# Motor-Z.net
KiCad netlist of a schematic drawn in Altium Designer
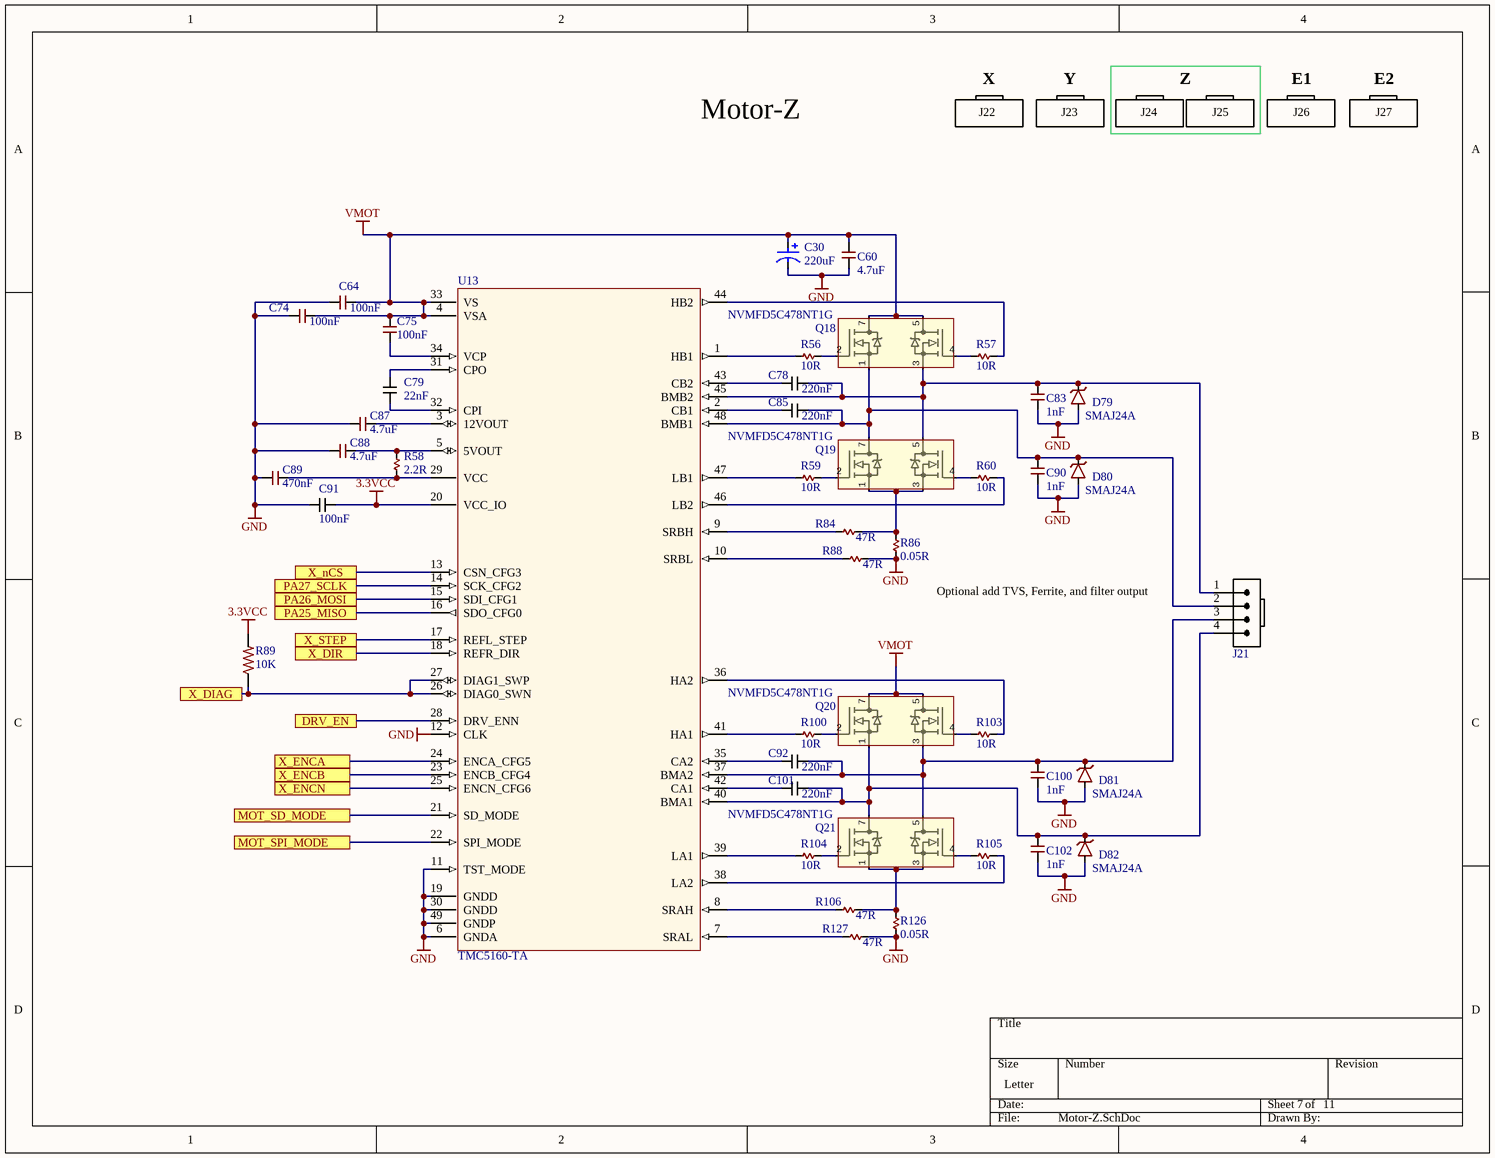
[diagram p0: Motor-Z.SchDoc]

(export (version "E")
  (design (tool "Eeschema 10.0.6"))
  (components
    (comp (ref "C30")
      (value "220uF")
      (footprint "CAP10X10")
      (description "CAP ALUM 220UF 20% 50V SMD")
      (fields (field (name "MANUFACTURER") "Nichicon") (field (name "TOLERANCE") "20%"))
      (libsource (lib "Capacitors") (part "220uF Al-El 50V"))
    )
    (comp (ref "C60")
      (value "4.7uF")
      (footprint "C1206")
      (description "CAP CER 1206 4.7uF 50V 10% X5R")
      (fields (field (name "MANUFACTURER") "Kemet") (field (name "PART") "4.7uF 50V X5R 1206"))
      (libsource (lib "Capacitors") (part "4.7uF 1206 50V X5R"))
    )
    (comp (ref "C64")
      (value "100nF")
      (footprint "C0603")
      (description "CAP CER 0603 100nF 50V 10% X7R")
      (fields (field (name "MANUFACTURER") "Kemet") (field (name "PART") "100nF 50V X7R 0603"))
      (libsource (lib "Capacitors") (part "100nF 0603 50V X7R"))
    )
    (comp (ref "C74")
      (value "100nF")
      (footprint "C0603")
      (description "CAP CER 0603 100nF 50V 10% X7R")
      (fields (field (name "MANUFACTURER") "Kemet") (field (name "PART") "100nF 50V X7R 0603"))
      (libsource (lib "Capacitors") (part "100nF 0603 50V X7R"))
    )
    (comp (ref "C75")
      (value "100nF")
      (footprint "C0603")
      (description "CAP CER 0603 100nF 50V 10% X7R")
      (fields (field (name "MANUFACTURER") "Kemet") (field (name "PART") "100nF 50V X7R 0603"))
      (libsource (lib "Capacitors") (part "100nF 0603 50V X7R"))
    )
    (comp (ref "C78")
      (value "220nF")
      (footprint "C0603")
      (description "CAP CER 0.22UF 50V X7R 0603")
      (fields (field (name "MANUFACTURER") "TDK"))
      (libsource (lib "Capacitors") (part "220nF 50V X7R 0603"))
    )
    (comp (ref "C79")
      (value "22nF")
      (footprint "C0603")
      (description "CAP CER 0.022UF 100V X7R 0603")
      (fields (field (name "MANUFACTURER") "Kemet"))
      (libsource (lib "Capacitors") (part "22nF 100V X7R 0603"))
    )
    (comp (ref "C83")
      (value "1nF")
      (footprint "C0603")
      (description "CAP CER 0603  1nF 50v 10% X7R")
      (fields (field (name "MANUFACTURER") "Kemet") (field (name "TOLERANCE") "+/- 10%"))
      (libsource (lib "Capacitors") (part "1nF 50V X7R 0603"))
    )
    (comp (ref "C85")
      (value "220nF")
      (footprint "C0603")
      (description "CAP CER 0.22UF 50V X7R 0603")
      (fields (field (name "MANUFACTURER") "TDK"))
      (libsource (lib "Capacitors") (part "220nF 50V X7R 0603"))
    )
    (comp (ref "C87")
      (value "4.7uF")
      (footprint "C1206")
      (description "CAP CER 1206 4.7uF 50V 10% X5R")
      (fields (field (name "MANUFACTURER") "Kemet") (field (name "PART") "4.7uF 50V X5R 1206"))
      (libsource (lib "Capacitors") (part "4.7uF 1206 50V X5R"))
    )
    (comp (ref "C88")
      (value "4.7uF")
      (footprint "C0603")
      (description "CAP CER 4.7UF 6.3V X7R 0603")
      (fields (field (name "MANUFACTURER") "Samsung") (field (name "TOLERANCE") "10%"))
      (libsource (lib "Capacitors") (part "4.7uF 0603 6.3V X7R"))
    )
    (comp (ref "C89")
      (value "470nF")
      (footprint "3Delight:C0402")
      (description "470nF 6.3v C0402 - GRM155R60J474KE19D")
      (fields (field (name "TOLERANCE") "10%") (field (name "MANUFACTURER") "Murata"))
      (libsource (lib "Capacitors") (part "470nF 0402 6.3V X5R"))
    )
    (comp (ref "C90")
      (value "1nF")
      (footprint "C0603")
      (description "CAP CER 0603  1nF 50v 10% X7R")
      (fields (field (name "MANUFACTURER") "Kemet") (field (name "TOLERANCE") "+/- 10%"))
      (libsource (lib "Capacitors") (part "1nF 50V X7R 0603"))
    )
    (comp (ref "C91")
      (value "100nF")
      (footprint "C0201 Large Pads")
      (description "CAP CER 0.1UF 6.3V 10% X5R 0201")
      (fields (field (name "MANUFACTURER") "Samsung") (field (name "TOLERANCE") "10%"))
      (libsource (lib "Capacitors") (part "100nF 6.3V X5R 0201"))
    )
    (comp (ref "C92")
      (value "220nF")
      (footprint "C0603")
      (description "CAP CER 0.22UF 50V X7R 0603")
      (fields (field (name "MANUFACTURER") "TDK"))
      (libsource (lib "Capacitors") (part "220nF 50V X7R 0603"))
    )
    (comp (ref "C100")
      (value "1nF")
      (footprint "C0603")
      (description "CAP CER 0603  1nF 50v 10% X7R")
      (fields (field (name "MANUFACTURER") "Kemet") (field (name "TOLERANCE") "+/- 10%"))
      (libsource (lib "Capacitors") (part "1nF 50V X7R 0603"))
    )
    (comp (ref "C101")
      (value "220nF")
      (footprint "C0603")
      (description "CAP CER 0.22UF 50V X7R 0603")
      (fields (field (name "MANUFACTURER") "TDK"))
      (libsource (lib "Capacitors") (part "220nF 50V X7R 0603"))
    )
    (comp (ref "C102")
      (value "1nF")
      (footprint "C0603")
      (description "CAP CER 0603  1nF 50v 10% X7R")
      (fields (field (name "MANUFACTURER") "Kemet") (field (name "TOLERANCE") "+/- 10%"))
      (libsource (lib "Capacitors") (part "1nF 50V X7R 0603"))
    )
    (comp (ref "D79")
      (value "SMAJ24A")
      (footprint "SMA-SM")
      (description "TVS DIODE 24V 38.9V SMA")
      (fields (field (name "MANUFACTURER") "Bourns Inc"))
      (libsource (lib "Diodes") (part "SMAJ24A"))
    )
    (comp (ref "D80")
      (value "SMAJ24A")
      (footprint "SMA-SM")
      (description "TVS DIODE 24V 38.9V SMA")
      (fields (field (name "MANUFACTURER") "Bourns Inc"))
      (libsource (lib "Diodes") (part "SMAJ24A"))
    )
    (comp (ref "D81")
      (value "SMAJ24A")
      (footprint "SMA-SM")
      (description "TVS DIODE 24V 38.9V SMA")
      (fields (field (name "MANUFACTURER") "Bourns Inc"))
      (libsource (lib "Diodes") (part "SMAJ24A"))
    )
    (comp (ref "D82")
      (value "SMAJ24A")
      (footprint "SMA-SM")
      (description "TVS DIODE 24V 38.9V SMA")
      (fields (field (name "MANUFACTURER") "Bourns Inc"))
      (libsource (lib "Diodes") (part "SMAJ24A"))
    )
    (comp (ref "J21")
      (value "Molex 0705430003")
      (footprint "4POL254 PIN-IN-PASTE")
      (description "Molex 4 Pin Clip Connector - Pin In Paste footprint")
      (libsource (lib "Connectors") (part "Molex 0705430003 PIP"))
    )
    (comp (ref "Q18")
      (value "NVMFD5C478NT1G")
      (footprint "SO8FL-Dual (DFN8 5x6, 1.26P Dual Flag)")
      (description "40V 17 MOHM T6 S08FL DUAL")
      (fields (field (name "MANUFACTURER") "ON Semiconductor") (field (name "TOLERANCE") "-NA-"))
      (libsource (lib "Transistors") (part "NVMFD5C478NT1G"))
    )
    (comp (ref "Q19")
      (value "NVMFD5C478NT1G")
      (footprint "SO8FL-Dual (DFN8 5x6, 1.26P Dual Flag)")
      (description "40V 17 MOHM T6 S08FL DUAL")
      (fields (field (name "MANUFACTURER") "ON Semiconductor") (field (name "TOLERANCE") "-NA-"))
      (libsource (lib "Transistors") (part "NVMFD5C478NT1G"))
    )
    (comp (ref "Q20")
      (value "NVMFD5C478NT1G")
      (footprint "SO8FL-Dual (DFN8 5x6, 1.26P Dual Flag)")
      (description "40V 17 MOHM T6 S08FL DUAL")
      (fields (field (name "MANUFACTURER") "ON Semiconductor") (field (name "TOLERANCE") "-NA-"))
      (libsource (lib "Transistors") (part "NVMFD5C478NT1G"))
    )
    (comp (ref "Q21")
      (value "NVMFD5C478NT1G")
      (footprint "SO8FL-Dual (DFN8 5x6, 1.26P Dual Flag)")
      (description "40V 17 MOHM T6 S08FL DUAL")
      (fields (field (name "MANUFACTURER") "ON Semiconductor") (field (name "TOLERANCE") "-NA-"))
      (libsource (lib "Transistors") (part "NVMFD5C478NT1G"))
    )
    (comp (ref "R56")
      (value "10R")
      (footprint "R0402")
      (description "RES SMD 10 OHM 1% 1/16W 0402")
      (fields (field (name "MANUFACTURER") "Yageo") (field (name "PART") "10R 1% 0402"))
      (libsource (lib "Resistors") (part "10R 1% 0402"))
    )
    (comp (ref "R57")
      (value "10R")
      (footprint "R0402")
      (description "RES SMD 10 OHM 1% 1/16W 0402")
      (fields (field (name "MANUFACTURER") "Yageo") (field (name "PART") "10R 1% 0402"))
      (libsource (lib "Resistors") (part "10R 1% 0402"))
    )
    (comp (ref "R58")
      (value "2.2R")
      (footprint "R0402")
      (description "RES SMD 2.2 OHM 5% 1/16W 0402")
      (fields (field (name "MANUFACTURER") "Yageo") (field (name "TOLERANCE") "+/- 5%"))
      (libsource (lib "Resistors") (part "2.2R 5% 0402"))
    )
    (comp (ref "R59")
      (value "10R")
      (footprint "R0402")
      (description "RES SMD 10 OHM 1% 1/16W 0402")
      (fields (field (name "MANUFACTURER") "Yageo") (field (name "PART") "10R 1% 0402"))
      (libsource (lib "Resistors") (part "10R 1% 0402"))
    )
    (comp (ref "R60")
      (value "10R")
      (footprint "R0402")
      (description "RES SMD 10 OHM 1% 1/16W 0402")
      (fields (field (name "MANUFACTURER") "Yageo") (field (name "PART") "10R 1% 0402"))
      (libsource (lib "Resistors") (part "10R 1% 0402"))
    )
    (comp (ref "R84")
      (value "47R")
      (footprint "R0402")
      (description "RES 47 OHM 1% 1/16W 0402")
      (fields (field (name "MANUFACTURER") "Vishay Dale") (field (name "TOLERANCE") "+/- 1%"))
      (libsource (lib "Resistors") (part "47R 1% 0402"))
    )
    (comp (ref "R86")
      (value "0.05R")
      (footprint "R2512")
      (description "RES 0.05 OHM 1% 2W 2512")
      (fields (field (name "MANUFACTURER") "Stackpole") (field (name "TOLERANCE") "+/- 1%"))
      (libsource (lib "Resistors") (part "0.05R 1% 2512"))
    )
    (comp (ref "R88")
      (value "47R")
      (footprint "R0402")
      (description "RES 47 OHM 1% 1/16W 0402")
      (fields (field (name "MANUFACTURER") "Vishay Dale") (field (name "TOLERANCE") "+/- 1%"))
      (libsource (lib "Resistors") (part "47R 1% 0402"))
    )
    (comp (ref "R89")
      (value "10K")
      (footprint "R0402")
      (description "RES SMD 10K OHM 1% 1/16W 0402")
      (fields (field (name "MANUFACTURER") "Yageo") (field (name "PART") "10k 1% 0402"))
      (libsource (lib "3Delight") (part "RC0402FR-0710KP"))
    )
    (comp (ref "R100")
      (value "10R")
      (footprint "R0402")
      (description "RES SMD 10 OHM 1% 1/16W 0402")
      (fields (field (name "MANUFACTURER") "Yageo") (field (name "PART") "10R 1% 0402"))
      (libsource (lib "Resistors") (part "10R 1% 0402"))
    )
    (comp (ref "R103")
      (value "10R")
      (footprint "R0402")
      (description "RES SMD 10 OHM 1% 1/16W 0402")
      (fields (field (name "MANUFACTURER") "Yageo") (field (name "PART") "10R 1% 0402"))
      (libsource (lib "Resistors") (part "10R 1% 0402"))
    )
    (comp (ref "R104")
      (value "10R")
      (footprint "R0402")
      (description "RES SMD 10 OHM 1% 1/16W 0402")
      (fields (field (name "MANUFACTURER") "Yageo") (field (name "PART") "10R 1% 0402"))
      (libsource (lib "Resistors") (part "10R 1% 0402"))
    )
    (comp (ref "R105")
      (value "10R")
      (footprint "R0402")
      (description "RES SMD 10 OHM 1% 1/16W 0402")
      (fields (field (name "MANUFACTURER") "Yageo") (field (name "PART") "10R 1% 0402"))
      (libsource (lib "Resistors") (part "10R 1% 0402"))
    )
    (comp (ref "R106")
      (value "47R")
      (footprint "R0402")
      (description "RES 47 OHM 1% 1/16W 0402")
      (fields (field (name "MANUFACTURER") "Vishay Dale") (field (name "TOLERANCE") "+/- 1%"))
      (libsource (lib "Resistors") (part "47R 1% 0402"))
    )
    (comp (ref "R126")
      (value "0.05R")
      (footprint "R2512")
      (description "RES 0.05 OHM 1% 2W 2512")
      (fields (field (name "MANUFACTURER") "Stackpole") (field (name "TOLERANCE") "+/- 1%"))
      (libsource (lib "Resistors") (part "0.05R 1% 2512"))
    )
    (comp (ref "R127")
      (value "47R")
      (footprint "R0402")
      (description "RES 47 OHM 1% 1/16W 0402")
      (fields (field (name "MANUFACTURER") "Vishay Dale") (field (name "TOLERANCE") "+/- 1%"))
      (libsource (lib "Resistors") (part "47R 1% 0402"))
    )
    (comp (ref "U13")
      (value "TMC5160-TA")
      (footprint "TQFP48-EP")
      (description "IC STEPPER MOTOR DVR TQFP48-EP")
      (fields (field (name "MANUFACTURER") "Trinamic"))
      (libsource (lib "ICs-Motor Controller") (part "TMC5160-TA"))
    )
  )
  (nets
    (net (code "1") (name "/DRV_EN") (class "Default")
      (node (ref "U13") (pin "28") (pinfunction "DRV_ENN_28") (pintype "input"))
    )
    (net (code "2") (name "/MOT_SD_MODE") (class "Default")
      (node (ref "U13") (pin "21") (pinfunction "SD_MODE_21") (pintype "input"))
    )
    (net (code "3") (name "/MOT_SPI_MODE") (class "Default")
      (node (ref "U13") (pin "22") (pinfunction "SPI_MODE_22") (pintype "input"))
    )
    (net (code "4") (name "/PA25_MISO") (class "Default")
      (node (ref "U13") (pin "16") (pinfunction "SDO_CFG0_16") (pintype "output"))
    )
    (net (code "5") (name "/PA26_MOSI") (class "Default")
      (node (ref "U13") (pin "15") (pinfunction "SDI_CFG1_15") (pintype "input"))
    )
    (net (code "6") (name "/PA27_SCLK") (class "Default")
      (node (ref "U13") (pin "14") (pinfunction "SCK_CFG2_14") (pintype "input"))
    )
    (net (code "7") (name "/X_DIAG") (class "Default")
      (node (ref "R89") (pin "1") (pinfunction "1_1") (pintype "passive"))
      (node (ref "U13") (pin "26") (pinfunction "DIAG0_SWN_26") (pintype "bidirectional"))
      (node (ref "U13") (pin "27") (pinfunction "DIAG1_SWP_27") (pintype "bidirectional"))
    )
    (net (code "8") (name "/X_DIR") (class "Default")
      (node (ref "U13") (pin "18") (pinfunction "REFR_DIR_18") (pintype "input"))
    )
    (net (code "9") (name "/X_ENCA") (class "Default")
      (node (ref "U13") (pin "24") (pinfunction "ENCA_CFG5_24") (pintype "input"))
    )
    (net (code "10") (name "/X_ENCB") (class "Default")
      (node (ref "U13") (pin "23") (pinfunction "ENCB_CFG4_23") (pintype "input"))
    )
    (net (code "11") (name "/X_ENCN") (class "Default")
      (node (ref "U13") (pin "25") (pinfunction "ENCN_CFG6_25") (pintype "input"))
    )
    (net (code "12") (name "/X_STEP") (class "Default")
      (node (ref "U13") (pin "17") (pinfunction "REFL_STEP_17") (pintype "input"))
    )
    (net (code "13") (name "/X_nCS") (class "Default")
      (node (ref "U13") (pin "13") (pinfunction "CSN_CFG3_13") (pintype "input"))
    )
    (net (code "14") (name "3.3VCC") (class "Default")
      (node (ref "C91") (pin "2") (pinfunction "2_2") (pintype "passive"))
      (node (ref "R89") (pin "2") (pinfunction "2_2") (pintype "passive"))
      (node (ref "U13") (pin "20") (pinfunction "VCC_IO_20") (pintype "power_in"))
    )
    (net (code "15") (name "GND") (class "Default")
      (node (ref "C100") (pin "1") (pinfunction "1_1") (pintype "passive"))
      (node (ref "C102") (pin "1") (pinfunction "1_1") (pintype "passive"))
      (node (ref "C30") (pin "2") (pinfunction "2_2") (pintype "passive"))
      (node (ref "C60") (pin "1") (pinfunction "1_1") (pintype "passive"))
      (node (ref "C64") (pin "1") (pinfunction "1_1") (pintype "passive"))
      (node (ref "C74") (pin "1") (pinfunction "1_1") (pintype "passive"))
      (node (ref "C83") (pin "1") (pinfunction "1_1") (pintype "passive"))
      (node (ref "C87") (pin "1") (pinfunction "1_1") (pintype "passive"))
      (node (ref "C88") (pin "1") (pinfunction "1_1") (pintype "passive"))
      (node (ref "C89") (pin "1") (pinfunction "1_1") (pintype "passive"))
      (node (ref "C90") (pin "1") (pinfunction "1_1") (pintype "passive"))
      (node (ref "C91") (pin "1") (pinfunction "1_1") (pintype "passive"))
      (node (ref "D79") (pin "A") (pinfunction "A_A") (pintype "passive"))
      (node (ref "D80") (pin "A") (pinfunction "A_A") (pintype "passive"))
      (node (ref "D81") (pin "A") (pinfunction "A_A") (pintype "passive"))
      (node (ref "D82") (pin "A") (pinfunction "A_A") (pintype "passive"))
      (node (ref "R126") (pin "1") (pinfunction "1_1") (pintype "passive"))
      (node (ref "R127") (pin "2") (pinfunction "2_2") (pintype "passive"))
      (node (ref "R86") (pin "1") (pinfunction "1_1") (pintype "passive"))
      (node (ref "R88") (pin "2") (pinfunction "2_2") (pintype "passive"))
      (node (ref "U13") (pin "11") (pinfunction "TST_MODE_11") (pintype "input"))
      (node (ref "U13") (pin "12") (pinfunction "CLK_12") (pintype "input"))
      (node (ref "U13") (pin "19") (pinfunction "GNDD_19") (pintype "power_in"))
      (node (ref "U13") (pin "30") (pinfunction "GNDD_30") (pintype "power_in"))
      (node (ref "U13") (pin "49") (pinfunction "GNDP_49") (pintype "power_in"))
      (node (ref "U13") (pin "6") (pinfunction "GNDA_6") (pintype "power_in"))
    )
    (net (code "16") (name "Net-(Q18-G1)") (class "Default")
      (node (ref "Q18") (pin "4") (pinfunction "G1_4") (pintype "passive"))
      (node (ref "R57") (pin "1") (pinfunction "1_1") (pintype "passive"))
    )
    (net (code "17") (name "Net-(Q18-G2)") (class "Default")
      (node (ref "Q18") (pin "2") (pinfunction "G2_2") (pintype "passive"))
      (node (ref "R56") (pin "2") (pinfunction "2_2") (pintype "passive"))
    )
    (net (code "18") (name "Net-(Q18-S1)") (class "Default")
      (node (ref "C78") (pin "2") (pinfunction "2_2") (pintype "passive"))
      (node (ref "C83") (pin "2") (pinfunction "2_2") (pintype "passive"))
      (node (ref "D79") (pin "K") (pinfunction "K_K") (pintype "passive"))
      (node (ref "J21") (pin "1") (pinfunction "1_1") (pintype "passive"))
      (node (ref "Q18") (pin "3") (pinfunction "S1_3") (pintype "passive"))
      (node (ref "Q19") (pin "5") (pinfunction "D1_5") (pintype "passive"))
      (node (ref "U13") (pin "45") (pinfunction "BMB2_45") (pintype "input"))
    )
    (net (code "19") (name "Net-(Q18-S2)") (class "Default")
      (node (ref "C85") (pin "2") (pinfunction "2_2") (pintype "passive"))
      (node (ref "C90") (pin "2") (pinfunction "2_2") (pintype "passive"))
      (node (ref "D80") (pin "K") (pinfunction "K_K") (pintype "passive"))
      (node (ref "J21") (pin "2") (pinfunction "2_2") (pintype "passive"))
      (node (ref "Q18") (pin "1") (pinfunction "S2_1") (pintype "passive"))
      (node (ref "Q19") (pin "7") (pinfunction "D2_7") (pintype "passive"))
      (node (ref "U13") (pin "48") (pinfunction "BMB1_48") (pintype "input"))
    )
    (net (code "20") (name "Net-(Q19-G1)") (class "Default")
      (node (ref "Q19") (pin "4") (pinfunction "G1_4") (pintype "passive"))
      (node (ref "R60") (pin "1") (pinfunction "1_1") (pintype "passive"))
    )
    (net (code "21") (name "Net-(Q19-G2)") (class "Default")
      (node (ref "Q19") (pin "2") (pinfunction "G2_2") (pintype "passive"))
      (node (ref "R59") (pin "2") (pinfunction "2_2") (pintype "passive"))
    )
    (net (code "22") (name "Net-(Q19-S1)") (class "Default")
      (node (ref "Q19") (pin "1") (pinfunction "S2_1") (pintype "passive"))
      (node (ref "Q19") (pin "3") (pinfunction "S1_3") (pintype "passive"))
      (node (ref "R84") (pin "2") (pinfunction "2_2") (pintype "passive"))
      (node (ref "R86") (pin "2") (pinfunction "2_2") (pintype "passive"))
    )
    (net (code "23") (name "Net-(Q20-G1)") (class "Default")
      (node (ref "Q20") (pin "4") (pinfunction "G1_4") (pintype "passive"))
      (node (ref "R103") (pin "1") (pinfunction "1_1") (pintype "passive"))
    )
    (net (code "24") (name "Net-(Q20-G2)") (class "Default")
      (node (ref "Q20") (pin "2") (pinfunction "G2_2") (pintype "passive"))
      (node (ref "R100") (pin "2") (pinfunction "2_2") (pintype "passive"))
    )
    (net (code "25") (name "Net-(Q20-S1)") (class "Default")
      (node (ref "C100") (pin "2") (pinfunction "2_2") (pintype "passive"))
      (node (ref "C92") (pin "2") (pinfunction "2_2") (pintype "passive"))
      (node (ref "D81") (pin "K") (pinfunction "K_K") (pintype "passive"))
      (node (ref "J21") (pin "3") (pinfunction "3_3") (pintype "passive"))
      (node (ref "Q20") (pin "3") (pinfunction "S1_3") (pintype "passive"))
      (node (ref "Q21") (pin "5") (pinfunction "D1_5") (pintype "passive"))
      (node (ref "U13") (pin "37") (pinfunction "BMA2_37") (pintype "input"))
    )
    (net (code "26") (name "Net-(Q20-S2)") (class "Default")
      (node (ref "C101") (pin "2") (pinfunction "2_2") (pintype "passive"))
      (node (ref "C102") (pin "2") (pinfunction "2_2") (pintype "passive"))
      (node (ref "D82") (pin "K") (pinfunction "K_K") (pintype "passive"))
      (node (ref "J21") (pin "4") (pinfunction "4_4") (pintype "passive"))
      (node (ref "Q20") (pin "1") (pinfunction "S2_1") (pintype "passive"))
      (node (ref "Q21") (pin "7") (pinfunction "D2_7") (pintype "passive"))
      (node (ref "U13") (pin "40") (pinfunction "BMA1_40") (pintype "input"))
    )
    (net (code "27") (name "Net-(Q21-G1)") (class "Default")
      (node (ref "Q21") (pin "4") (pinfunction "G1_4") (pintype "passive"))
      (node (ref "R105") (pin "1") (pinfunction "1_1") (pintype "passive"))
    )
    (net (code "28") (name "Net-(Q21-G2)") (class "Default")
      (node (ref "Q21") (pin "2") (pinfunction "G2_2") (pintype "passive"))
      (node (ref "R104") (pin "2") (pinfunction "2_2") (pintype "passive"))
    )
    (net (code "29") (name "Net-(Q21-S1)") (class "Default")
      (node (ref "Q21") (pin "1") (pinfunction "S2_1") (pintype "passive"))
      (node (ref "Q21") (pin "3") (pinfunction "S1_3") (pintype "passive"))
      (node (ref "R106") (pin "2") (pinfunction "2_2") (pintype "passive"))
      (node (ref "R126") (pin "2") (pinfunction "2_2") (pintype "passive"))
    )
    (net (code "30") (name "Net-(U13-5VOUT)") (class "Default")
      (node (ref "C88") (pin "2") (pinfunction "2_2") (pintype "passive"))
      (node (ref "R58") (pin "2") (pinfunction "2_2") (pintype "passive"))
      (node (ref "U13") (pin "5") (pinfunction "5VOUT_5") (pintype "bidirectional"))
    )
    (net (code "31") (name "Net-(U13-12VOUT)") (class "Default")
      (node (ref "C87") (pin "2") (pinfunction "2_2") (pintype "passive"))
      (node (ref "U13") (pin "3") (pinfunction "12VOUT_3") (pintype "bidirectional"))
    )
    (net (code "32") (name "Net-(U13-CA1)") (class "Default")
      (node (ref "C101") (pin "1") (pinfunction "1_1") (pintype "passive"))
      (node (ref "U13") (pin "42") (pinfunction "CA1_42") (pintype "input"))
    )
    (net (code "33") (name "Net-(U13-CA2)") (class "Default")
      (node (ref "C92") (pin "1") (pinfunction "1_1") (pintype "passive"))
      (node (ref "U13") (pin "35") (pinfunction "CA2_35") (pintype "input"))
    )
    (net (code "34") (name "Net-(U13-CB1)") (class "Default")
      (node (ref "C85") (pin "1") (pinfunction "1_1") (pintype "passive"))
      (node (ref "U13") (pin "2") (pinfunction "CB1_2") (pintype "input"))
    )
    (net (code "35") (name "Net-(U13-CB2)") (class "Default")
      (node (ref "C78") (pin "1") (pinfunction "1_1") (pintype "passive"))
      (node (ref "U13") (pin "43") (pinfunction "CB2_43") (pintype "input"))
    )
    (net (code "36") (name "Net-(U13-CPI)") (class "Default")
      (node (ref "C79") (pin "1") (pinfunction "1_1") (pintype "passive"))
      (node (ref "U13") (pin "32") (pinfunction "CPI_32") (pintype "input"))
    )
    (net (code "37") (name "Net-(U13-CPO)") (class "Default")
      (node (ref "C79") (pin "2") (pinfunction "2_2") (pintype "passive"))
      (node (ref "U13") (pin "31") (pinfunction "CPO_31") (pintype "input"))
    )
    (net (code "38") (name "Net-(U13-HA1)") (class "Default")
      (node (ref "R100") (pin "1") (pinfunction "1_1") (pintype "passive"))
      (node (ref "U13") (pin "41") (pinfunction "HA1_41") (pintype "output"))
    )
    (net (code "39") (name "Net-(U13-HA2)") (class "Default")
      (node (ref "R103") (pin "2") (pinfunction "2_2") (pintype "passive"))
      (node (ref "U13") (pin "36") (pinfunction "HA2_36") (pintype "output"))
    )
    (net (code "40") (name "Net-(U13-HB1)") (class "Default")
      (node (ref "R56") (pin "1") (pinfunction "1_1") (pintype "passive"))
      (node (ref "U13") (pin "1") (pinfunction "HB1_1") (pintype "output"))
    )
    (net (code "41") (name "Net-(U13-HB2)") (class "Default")
      (node (ref "R57") (pin "2") (pinfunction "2_2") (pintype "passive"))
      (node (ref "U13") (pin "44") (pinfunction "HB2_44") (pintype "output"))
    )
    (net (code "42") (name "Net-(U13-LA1)") (class "Default")
      (node (ref "R104") (pin "1") (pinfunction "1_1") (pintype "passive"))
      (node (ref "U13") (pin "39") (pinfunction "LA1_39") (pintype "output"))
    )
    (net (code "43") (name "Net-(U13-LA2)") (class "Default")
      (node (ref "R105") (pin "2") (pinfunction "2_2") (pintype "passive"))
      (node (ref "U13") (pin "38") (pinfunction "LA2_38") (pintype "output"))
    )
    (net (code "44") (name "Net-(U13-LB1)") (class "Default")
      (node (ref "R59") (pin "1") (pinfunction "1_1") (pintype "passive"))
      (node (ref "U13") (pin "47") (pinfunction "LB1_47") (pintype "output"))
    )
    (net (code "45") (name "Net-(U13-LB2)") (class "Default")
      (node (ref "R60") (pin "2") (pinfunction "2_2") (pintype "passive"))
      (node (ref "U13") (pin "46") (pinfunction "LB2_46") (pintype "output"))
    )
    (net (code "46") (name "Net-(U13-SRAH)") (class "Default")
      (node (ref "R106") (pin "1") (pinfunction "1_1") (pintype "passive"))
      (node (ref "U13") (pin "8") (pinfunction "SRAH_8") (pintype "input"))
    )
    (net (code "47") (name "Net-(U13-SRAL)") (class "Default")
      (node (ref "R127") (pin "1") (pinfunction "1_1") (pintype "passive"))
      (node (ref "U13") (pin "7") (pinfunction "SRAL_7") (pintype "input"))
    )
    (net (code "48") (name "Net-(U13-SRBH)") (class "Default")
      (node (ref "R84") (pin "1") (pinfunction "1_1") (pintype "passive"))
      (node (ref "U13") (pin "9") (pinfunction "SRBH_9") (pintype "input"))
    )
    (net (code "49") (name "Net-(U13-SRBL)") (class "Default")
      (node (ref "R88") (pin "1") (pinfunction "1_1") (pintype "passive"))
      (node (ref "U13") (pin "10") (pinfunction "SRBL_10") (pintype "input"))
    )
    (net (code "50") (name "Net-(U13-VCC)") (class "Default")
      (node (ref "C89") (pin "2") (pinfunction "2_2") (pintype "passive"))
      (node (ref "R58") (pin "1") (pinfunction "1_1") (pintype "passive"))
      (node (ref "U13") (pin "29") (pinfunction "VCC_29") (pintype "power_in"))
    )
    (net (code "51") (name "Net-(U13-VCP)") (class "Default")
      (node (ref "C75") (pin "1") (pinfunction "1_1") (pintype "passive"))
      (node (ref "U13") (pin "34") (pinfunction "VCP_34") (pintype "input"))
    )
    (net (code "52") (name "VMOT") (class "Default")
      (node (ref "C30") (pin "1") (pinfunction "1_1") (pintype "passive"))
      (node (ref "C60") (pin "2") (pinfunction "2_2") (pintype "passive"))
      (node (ref "C64") (pin "2") (pinfunction "2_2") (pintype "passive"))
      (node (ref "C74") (pin "2") (pinfunction "2_2") (pintype "passive"))
      (node (ref "C75") (pin "2") (pinfunction "2_2") (pintype "passive"))
      (node (ref "Q18") (pin "5") (pinfunction "D1_5") (pintype "passive"))
      (node (ref "Q18") (pin "7") (pinfunction "D2_7") (pintype "passive"))
      (node (ref "Q20") (pin "5") (pinfunction "D1_5") (pintype "passive"))
      (node (ref "Q20") (pin "7") (pinfunction "D2_7") (pintype "passive"))
      (node (ref "U13") (pin "33") (pinfunction "VS_33") (pintype "power_in"))
      (node (ref "U13") (pin "4") (pinfunction "VSA_4") (pintype "power_in"))
    )
  )
)
